# Power.net
KiCad netlist of a schematic drawn in Altium Designer
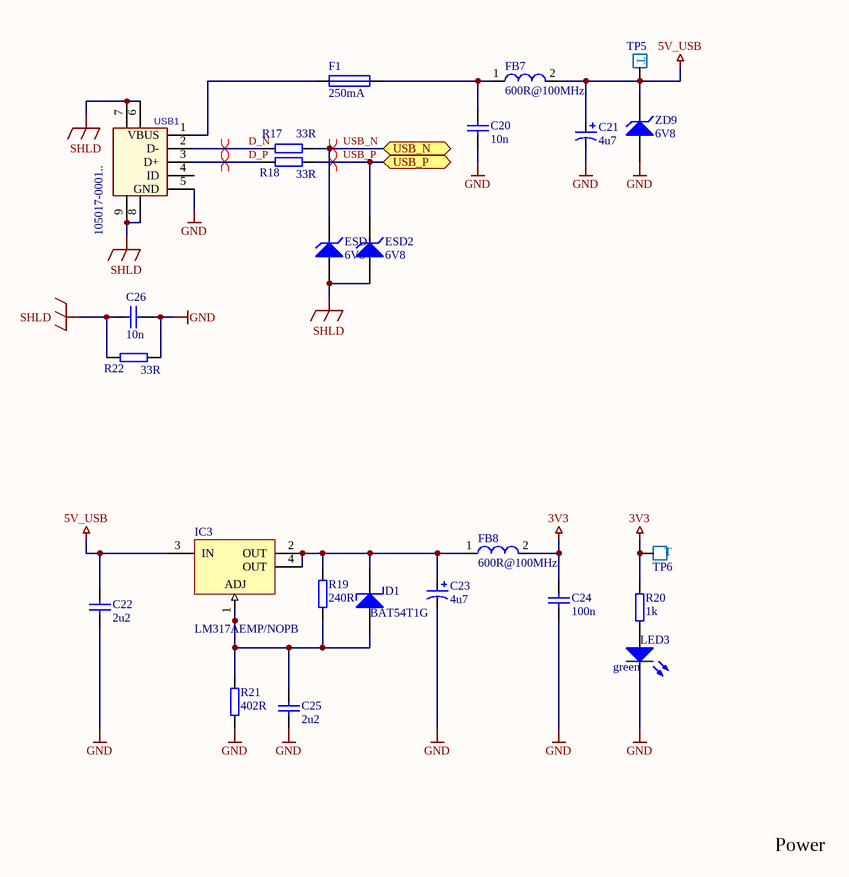
[diagram p0: Power.SchDoc]

(export (version "E")
  (design (tool "Eeschema 10.0.6"))
  (components
    (comp (ref "C20")
      (value "10n")
      (footprint "SMD_C0603")
      (description "Capacitor")
      (libsource (lib "WatchDogAlarm_rev1_3") (part "CAP"))
    )
    (comp (ref "C21")
      (value "4u7")
      (footprint "Tantalum 3216")
      (description "Generic polarized capacitor")
      (libsource (lib "WatchDogAlarm_rev1_3") (part "Capacitor - polarized"))
    )
    (comp (ref "C22")
      (value "2u2")
      (footprint "SMD_C0805")
      (description "Capacitor")
      (libsource (lib "WatchDogAlarm_rev1_3") (part "CAP"))
    )
    (comp (ref "C23")
      (value "4u7")
      (footprint "Tantalum 3216")
      (description "Generic polarized capacitor")
      (libsource (lib "WatchDogAlarm_rev1_3") (part "Capacitor - polarized"))
    )
    (comp (ref "C24")
      (value "100n")
      (footprint "SMD_C0603")
      (description "Capacitor")
      (libsource (lib "WatchDogAlarm_rev1_3") (part "CAP"))
    )
    (comp (ref "C25")
      (value "2u2")
      (footprint "SMD_C0805")
      (description "Capacitor")
      (libsource (lib "WatchDogAlarm_rev1_3") (part "CAP"))
    )
    (comp (ref "C26")
      (value "10n")
      (footprint "SMD_C0603")
      (description "Capacitor")
      (libsource (lib "WatchDogAlarm_rev1_3") (part "CAP"))
    )
    (comp (ref "D1")
      (value "BAT54T1G")
      (footprint "SOD-123")
      (fields (field (name "MANUFACTURER") "ON SEMICONDUCTOR"))
      (libsource (lib "WatchDogAlarm_rev1_3") (part "DIODE_SCHOTTKY"))
    )
    (comp (ref "ESD1")
      (value "6V8")
      (footprint "SMD_R0603")
      (description "ESD Protection device")
      (fields (field (name "MANUFACTURER") "ON Semiconductor") (field (name "PARTNUMBER") "BZX84C6V8LT1G"))
      (libsource (lib "WatchDogAlarm_rev1_3") (part "ZenerDiode"))
    )
    (comp (ref "ESD2")
      (value "6V8")
      (footprint "SMD_R0603")
      (description "ESD Protection device")
      (fields (field (name "MANUFACTURER") "ON Semiconductor") (field (name "PARTNUMBER") "BZX84C6V8LT1G"))
      (libsource (lib "WatchDogAlarm_rev1_3") (part "ZenerDiode"))
    )
    (comp (ref "F1")
      (value "250mA")
      (footprint "PPTCF 1206")
      (description "Resettable Fuse, PPTC, 1206 (3216 Metric), POLYFUSE 1206L Series, 16 VDC, 250 mA, 500 mA, 0.08 s")
      (fields (field (name "MANUFACTURER") "Littelfuse"))
      (libsource (lib "WatchDogAlarm_rev1_3") (part "PolyFuse"))
    )
    (comp (ref "FB7")
      (value "600R@100MHz")
      (footprint "SMD_R0603")
      (description "Ferrite bead")
      (libsource (lib "WatchDogAlarm_rev1_3") (part "FB"))
    )
    (comp (ref "FB8")
      (value "600R@100MHz")
      (footprint "SMD_R0603")
      (description "Ferrite bead")
      (libsource (lib "WatchDogAlarm_rev1_3") (part "FB"))
    )
    (comp (ref "IC3")
      (value "LM317AEMP/NOPB")
      (footprint "SOT-223")
      (description "3-Terminal Adjustable Regulator")
      (fields (field (name "MANUFACTURER") "TEXAS INSTRUMENTS"))
      (libsource (lib "WatchDogAlarm_rev1_3") (part "LM317KC"))
    )
    (comp (ref "LED3") (value "green") (footprint "SMD_LD0603") (libsource (lib "Atlan") (part "LED")))
    (comp (ref "R17")
      (value "33R")
      (footprint "SMD_R0603")
      (libsource (lib "WatchDogAlarm_rev1_3") (part "RESISTOR"))
    )
    (comp (ref "R18")
      (value "33R")
      (footprint "SMD_R0603")
      (libsource (lib "WatchDogAlarm_rev1_3") (part "RESISTOR"))
    )
    (comp (ref "R19")
      (value "240R")
      (footprint "SMD_R0603")
      (libsource (lib "WatchDogAlarm_rev1_3") (part "RESISTOR"))
    )
    (comp (ref "R20")
      (value "1k")
      (footprint "SMD_R0603")
      (libsource (lib "WatchDogAlarm_rev1_3") (part "RESISTOR"))
    )
    (comp (ref "R21")
      (value "402R")
      (footprint "SMD_R0603")
      (libsource (lib "WatchDogAlarm_rev1_3") (part "RESISTOR"))
    )
    (comp (ref "R22")
      (value "33R")
      (footprint "SMD_R0603")
      (libsource (lib "WatchDogAlarm_rev1_3") (part "RESISTOR"))
    )
    (comp (ref "TP5")
      (value "TEST_PAD_1.5mm")
      (footprint "TEST_PAD_1.5mm")
      (libsource (lib "Atlan") (part "TEST_PAD"))
    )
    (comp (ref "TP6")
      (value "TEST_PAD_1.5mm")
      (footprint "TEST_PAD_1.5mm")
      (libsource (lib "Atlan") (part "TEST_PAD"))
    )
    (comp (ref "USB1")
      (value "105017-0001..")
      (footprint "USB_MICRO_B")
      (fields (field (name "MANUFACTURER") "MOLEX"))
      (libsource (lib "unidisp43_r1.0") (part "Micro_USB_MIUSB-F5M-BB-U"))
    )
    (comp (ref "ZD9")
      (value "6V8")
      (footprint "SOT-23")
      (description "Zener Diode")
      (fields (field (name "MANUFACTURER") "ON Semiconductor") (field (name "PARTNUMBER") "BZX84C6V8LT1G"))
      (libsource (lib "WatchDogAlarm_rev1_3") (part "ZenerDiode"))
    )
  )
  (nets
    (net (code "1") (name "/D_N") (class "Default")
      (node (ref "R17") (pin "2") (pintype "passive"))
      (node (ref "USB1") (pin "2") (pinfunction "D-_2") (pintype "passive"))
    )
    (net (code "2") (name "/D_P") (class "Default")
      (node (ref "R18") (pin "2") (pintype "passive"))
      (node (ref "USB1") (pin "3") (pinfunction "D+_3") (pintype "passive"))
    )
    (net (code "3") (name "/USB_N") (class "Default")
      (node (ref "ESD1") (pin "3") (pinfunction "K_3") (pintype "passive"))
      (node (ref "R17") (pin "1") (pintype "passive"))
    )
    (net (code "4") (name "/USB_P") (class "Default")
      (node (ref "ESD2") (pin "3") (pinfunction "K_3") (pintype "passive"))
      (node (ref "R18") (pin "1") (pintype "passive"))
    )
    (net (code "5") (name "3V3") (class "Default")
      (node (ref "C24") (pin "2") (pinfunction "2_2") (pintype "passive"))
      (node (ref "FB8") (pin "2") (pinfunction "2_2") (pintype "passive"))
      (node (ref "R20") (pin "2") (pintype "passive"))
      (node (ref "TP6") (pin "1") (pintype "passive"))
    )
    (net (code "6") (name "5V_USB") (class "Default")
      (node (ref "C21") (pin "1") (pinfunction "1_1") (pintype "passive"))
      (node (ref "C22") (pin "2") (pinfunction "2_2") (pintype "passive"))
      (node (ref "FB7") (pin "2") (pinfunction "2_2") (pintype "passive"))
      (node (ref "IC3") (pin "3") (pinfunction "IN_3") (pintype "power_in"))
      (node (ref "TP5") (pin "1") (pintype "passive"))
      (node (ref "ZD9") (pin "3") (pinfunction "K_3") (pintype "passive"))
    )
    (net (code "7") (name "GND") (class "Default")
      (node (ref "C20") (pin "1") (pinfunction "1_1") (pintype "passive"))
      (node (ref "C21") (pin "2") (pinfunction "2_2") (pintype "passive"))
      (node (ref "C22") (pin "1") (pinfunction "1_1") (pintype "passive"))
      (node (ref "C23") (pin "2") (pinfunction "2_2") (pintype "passive"))
      (node (ref "C24") (pin "1") (pinfunction "1_1") (pintype "passive"))
      (node (ref "C25") (pin "1") (pinfunction "1_1") (pintype "passive"))
      (node (ref "C26") (pin "1") (pinfunction "1_1") (pintype "passive"))
      (node (ref "LED3") (pin "1") (pinfunction "K_1") (pintype "passive"))
      (node (ref "R21") (pin "1") (pintype "passive"))
      (node (ref "R22") (pin "1") (pintype "passive"))
      (node (ref "USB1") (pin "5") (pinfunction "GND_5") (pintype "power_in"))
      (node (ref "ZD9") (pin "1") (pinfunction "A_1") (pintype "passive"))
    )
    (net (code "8") (name "Net-(C20-Pad2)") (class "Default")
      (node (ref "C20") (pin "2") (pinfunction "2_2") (pintype "passive"))
      (node (ref "F1") (pin "2") (pinfunction "2_2") (pintype "passive"))
      (node (ref "FB7") (pin "1") (pinfunction "1_1") (pintype "passive"))
    )
    (net (code "9") (name "Net-(D1-A)") (class "Default")
      (node (ref "C25") (pin "2") (pinfunction "2_2") (pintype "passive"))
      (node (ref "D1") (pin "2") (pinfunction "A_2") (pintype "passive"))
      (node (ref "IC3") (pin "1") (pinfunction "ADJ_1") (pintype "input"))
      (node (ref "R19") (pin "1") (pintype "passive"))
      (node (ref "R21") (pin "2") (pintype "passive"))
    )
    (net (code "10") (name "Net-(D1-K)") (class "Default")
      (node (ref "C23") (pin "1") (pinfunction "1_1") (pintype "passive"))
      (node (ref "D1") (pin "1") (pinfunction "K_1") (pintype "passive"))
      (node (ref "FB8") (pin "1") (pinfunction "1_1") (pintype "passive"))
      (node (ref "IC3") (pin "2") (pinfunction "OUT_2") (pintype "power_in"))
      (node (ref "IC3") (pin "4") (pinfunction "OUT_4") (pintype "power_in"))
      (node (ref "R19") (pin "2") (pintype "passive"))
    )
    (net (code "11") (name "Net-(LED3-A)") (class "Default")
      (node (ref "LED3") (pin "2") (pinfunction "A_2") (pintype "passive"))
      (node (ref "R20") (pin "1") (pintype "passive"))
    )
    (net (code "12") (name "Net-(USB1-VBUS)") (class "Default")
      (node (ref "F1") (pin "1") (pinfunction "1_1") (pintype "passive"))
      (node (ref "USB1") (pin "1") (pinfunction "VBUS_1") (pintype "power_in"))
    )
    (net (code "13") (name "SHLD") (class "Default")
      (node (ref "C26") (pin "2") (pinfunction "2_2") (pintype "passive"))
      (node (ref "ESD1") (pin "1") (pinfunction "A_1") (pintype "passive"))
      (node (ref "ESD2") (pin "1") (pinfunction "A_1") (pintype "passive"))
      (node (ref "R22") (pin "2") (pintype "passive"))
      (node (ref "USB1") (pin "6") (pinfunction "GND1_6") (pintype "passive"))
      (node (ref "USB1") (pin "7") (pinfunction "GND2_7") (pintype "passive"))
      (node (ref "USB1") (pin "8") (pinfunction "GND2_8") (pintype "passive"))
      (node (ref "USB1") (pin "9") (pinfunction "GND3_9") (pintype "passive"))
    )
    (net (code "14") (name "unconnected-(USB1-ID-Pad4)") (class "Default")
      (node (ref "USB1") (pin "4") (pinfunction "ID_4") (pintype "passive"))
    )
  )
)
